# Energy_harvesting.net
KiCad netlist of a schematic drawn in Altium Designer
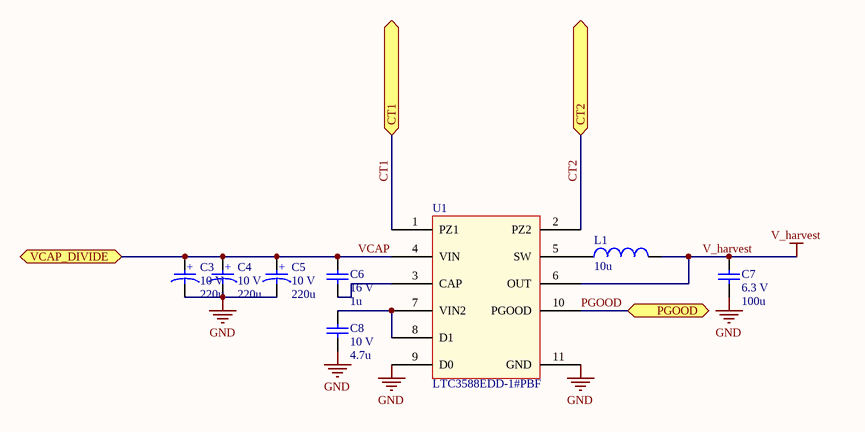
[diagram p0: Energy_harvesting.SchDoc]

(export (version "E")
  (design (tool "Eeschema 10.0.6"))
  (components
    (comp (ref "C3")
      (value "220u")
      (footprint "2312")
      (description "220µF ±10% Molded Tantalum Capacitors 10V 2312")
      (fields
        (field (name "TOLERANCE") "10%")
        (field (name "VOLTAGE RATED") "10 V")
        (field (name "MANUFACTURER PART NUMBER") "TAJC227K010RNJ")
      )
      (libsource (lib "capacitors") (part "TAJC227K010RNJ"))
    )
    (comp (ref "C4")
      (value "220u")
      (footprint "2312")
      (description "220µF ±10% Molded Tantalum Capacitors 10V 2312")
      (fields
        (field (name "TOLERANCE") "10%")
        (field (name "VOLTAGE RATED") "10 V")
        (field (name "MANUFACTURER PART NUMBER") "TAJC227K010RNJ")
      )
      (libsource (lib "capacitors") (part "TAJC227K010RNJ"))
    )
    (comp (ref "C5")
      (value "220u")
      (footprint "2312")
      (description "220µF ±10% Molded Tantalum Capacitors 10V 2312")
      (fields
        (field (name "TOLERANCE") "10%")
        (field (name "VOLTAGE RATED") "10 V")
        (field (name "MANUFACTURER PART NUMBER") "TAJC227K010RNJ")
      )
      (libsource (lib "capacitors") (part "TAJC227K010RNJ"))
    )
    (comp (ref "C6")
      (value "1u")
      (footprint "0402")
      (description "1µF ±10% 16V Ceramic Capacitor X6S 0402")
      (fields
        (field (name "VOLTAGE RATED") "16 V")
        (field (name "TOLERANCE") "10%")
        (field (name "MANUFACTURER PART NUMBER") "C1005X6S1C105K050BC")
      )
      (libsource (lib "capacitors") (part "C1005X6S1C105K050BC"))
    )
    (comp (ref "C7")
      (value "100u")
      (footprint "1206")
      (description "100µF ±20% 6.3V Ceramic Capacitor X5R 1206")
      (fields
        (field (name "VOLTAGE RATED") "6.3 V")
        (field (name "TOLERANCE") "20%")
        (field (name "MANUFACTURER PART NUMBER") "GRM31CR60J107ME39K")
      )
      (libsource (lib "capacitors") (part "GRM31CR60J107ME39K"))
    )
    (comp (ref "C8")
      (value "4.7u")
      (footprint "0603")
      (description "4.7µF ±10% 10V Ceramic Capacitor X5R 0603")
      (fields
        (field (name "TOLERANCE") "10%")
        (field (name "VOLTAGE RATED") "10 V")
        (field (name "MANUFACTURER PART NUMBER") "CGB3B1X5R1A475K055AC")
      )
      (libsource (lib "capacitors") (part "CGB3B1X5R1A475K055AC"))
    )
    (comp (ref "L1")
      (value "10u")
      (footprint "CDRH2D18")
      (description "10µH Shielded Inductor 1A 180 mOhm Max Nonstandard")
      (fields
        (field (name "TOLERANCE") "30%")
        (field (name "MANUFACTURER PART NUMBER") "CDRH2D18/LDNP-100NC")
      )
      (libsource (lib "inductors") (part "CDRH2D18/LDNP-100NC"))
    )
    (comp (ref "U1")
      (value "LTC3588EDD-1#PBF")
      (footprint "QFN-10")
      (description "Piezoelectric Energy Harvesting Power Supply")
      (libsource (lib "voltage regulator") (part "LTC3588EDD-1#PBF"))
    )
  )
  (nets
    (net (code "1") (name "/CT1") (class "Default")
      (node (ref "U1") (pin "1") (pinfunction "PZ1_1") (pintype "passive"))
    )
    (net (code "2") (name "/CT2") (class "Default")
      (node (ref "U1") (pin "2") (pinfunction "PZ2_2") (pintype "passive"))
    )
    (net (code "3") (name "/PGOOD") (class "Default")
      (node (ref "U1") (pin "10") (pinfunction "PGOOD_10") (pintype "passive"))
    )
    (net (code "4") (name "/VCAP") (class "Default")
      (node (ref "C3") (pin "1") (pintype "passive"))
      (node (ref "C4") (pin "1") (pintype "passive"))
      (node (ref "C5") (pin "1") (pintype "passive"))
      (node (ref "C6") (pin "1") (pintype "passive"))
      (node (ref "U1") (pin "4") (pinfunction "VIN_4") (pintype "passive"))
    )
    (net (code "5") (name "GND") (class "Default")
      (node (ref "C3") (pin "2") (pintype "passive"))
      (node (ref "C4") (pin "2") (pintype "passive"))
      (node (ref "C5") (pin "2") (pintype "passive"))
      (node (ref "C7") (pin "2") (pintype "passive"))
      (node (ref "C8") (pin "2") (pintype "passive"))
      (node (ref "U1") (pin "11") (pinfunction "GND_11") (pintype "passive"))
      (node (ref "U1") (pin "9") (pinfunction "D0_9") (pintype "passive"))
    )
    (net (code "6") (name "Net-(U1-CAP)") (class "Default")
      (node (ref "C6") (pin "2") (pintype "passive"))
      (node (ref "U1") (pin "3") (pinfunction "CAP_3") (pintype "passive"))
    )
    (net (code "7") (name "Net-(U1-D1)") (class "Default")
      (node (ref "C8") (pin "1") (pintype "passive"))
      (node (ref "U1") (pin "7") (pinfunction "VIN2_7") (pintype "passive"))
      (node (ref "U1") (pin "8") (pinfunction "D1_8") (pintype "passive"))
    )
    (net (code "8") (name "Net-(U1-SW)") (class "Default")
      (node (ref "L1") (pin "2") (pintype "passive"))
      (node (ref "U1") (pin "5") (pinfunction "SW_5") (pintype "passive"))
    )
    (net (code "9") (name "V_harvest") (class "Default")
      (node (ref "C7") (pin "1") (pintype "passive"))
      (node (ref "L1") (pin "1") (pintype "passive"))
      (node (ref "U1") (pin "6") (pinfunction "OUT_6") (pintype "passive"))
    )
  )
)
